# 6502_Debugger_2020-04-26_19-41-09.net
KiCad netlist of a schematic drawn in EasyEDA
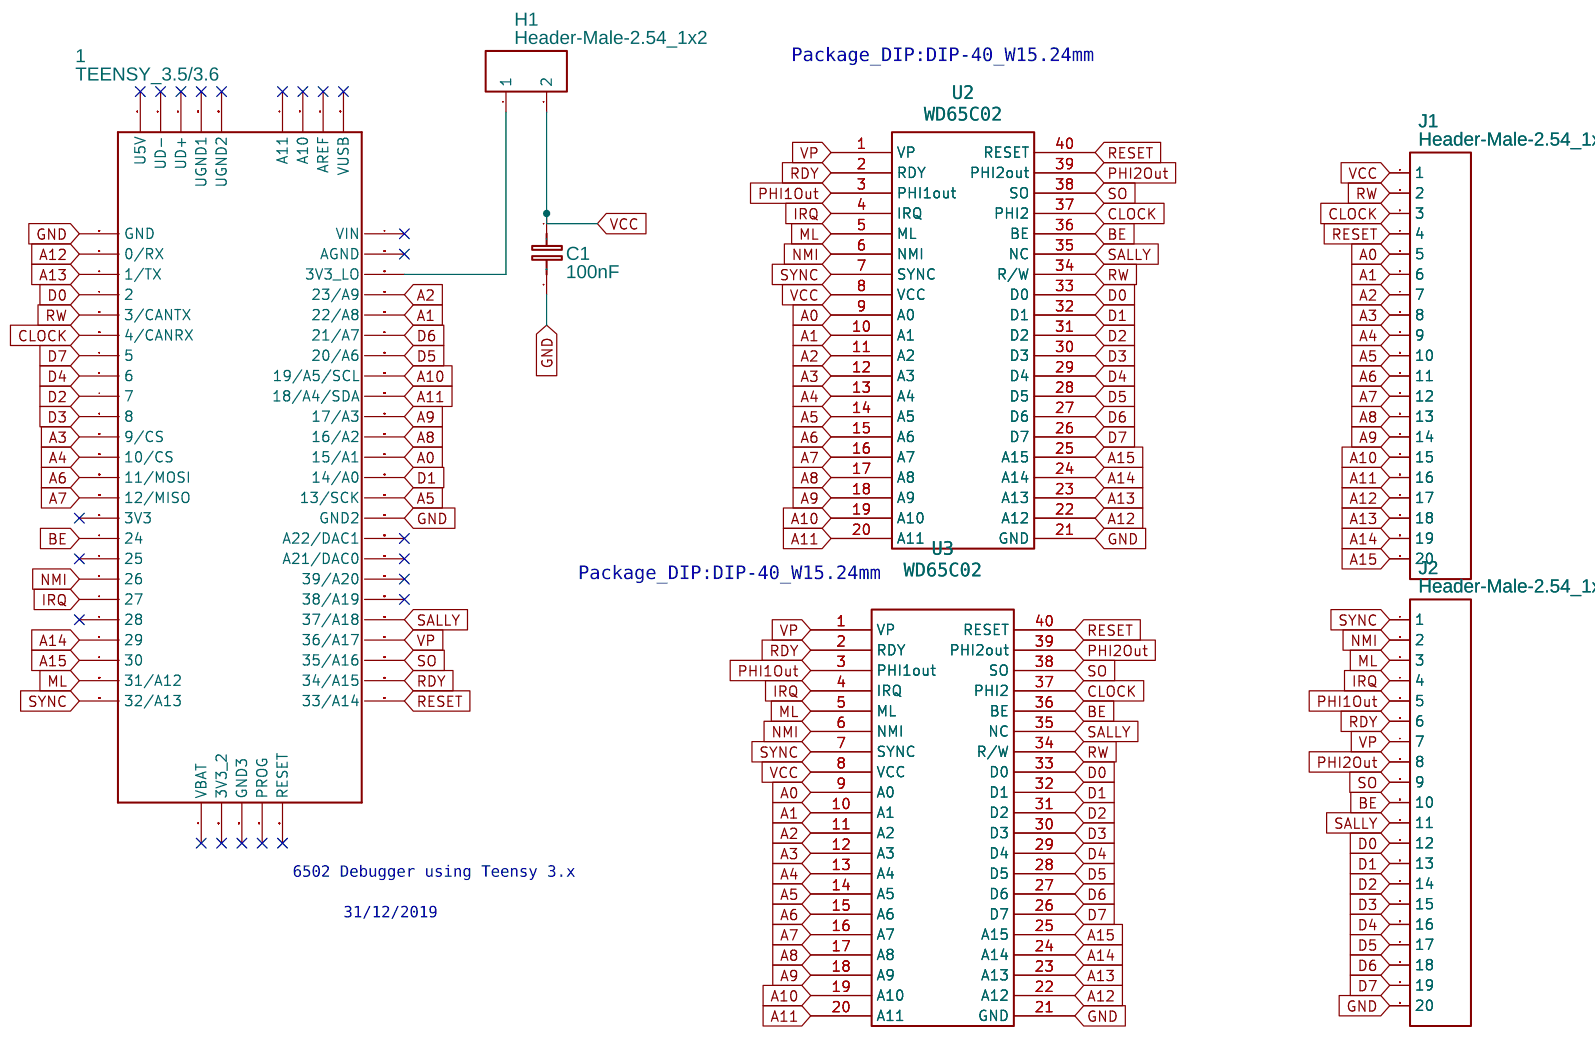
[diagram p0: schematic sheet]

(export (version "E")
  (design (tool "Eeschema 10.0.6"))
  (components
    (comp (ref "1") (value "TEENSY_3.5/3.6") (libsource (lib "") (part "TEENSY_3.5/3.6")))
    (comp (ref "C1") (value "100nF") (libsource (lib "") (part "Cap_RAD-0.1_EU")))
    (comp (ref "H1")
      (value "Header-Male-2.54_1x2")
      (fields (field (name "BOM_Manufacturer Part") "826629-2") (field (name "BOM_Supplier Part") "C86471"))
      (libsource (lib "") (part "Header-Male-2.54_1x2"))
    )
    (comp (ref "J1")
      (value "Header-Male-2.54_1x20")
      (fields
        (field (name "BOM_Manufacturer Part") "2.54mm 1*20PHeader")
        (field (name "BOM_Supplier Part") "C50981")
      )
      (libsource (lib "") (part "Header-Male-2.54_1x20"))
    )
    (comp (ref "J2")
      (value "Header-Male-2.54_1x20")
      (fields
        (field (name "BOM_Manufacturer Part") "2.54mm 1*20PHeader")
        (field (name "BOM_Supplier Part") "C50981")
      )
      (libsource (lib "") (part "Header-Male-2.54_1x20"))
    )
    (comp (ref "U2") (value "WD65C02") (libsource (lib "") (part "Unknown_560_230")))
    (comp (ref "U3") (value "WD65C02") (libsource (lib "") (part "Unknown_550_465")))
  )
  (nets
    (net (code "1") (name "A0") (class "Default")
      (node (ref "1") (pin "15/A1") (pinfunction "15/A1_15/A1") (pintype "bidirectional"))
      (node (ref "J1") (pin "5") (pinfunction "5_5") (pintype "input"))
      (node (ref "U2") (pin "9") (pinfunction "A0_9") (pintype "output"))
      (node (ref "U3") (pin "9") (pinfunction "A0_9") (pintype "output"))
    )
    (net (code "2") (name "A1") (class "Default")
      (node (ref "1") (pin "22/A8") (pinfunction "22/A8_22/A8") (pintype "bidirectional"))
      (node (ref "J1") (pin "6") (pinfunction "6_6") (pintype "input"))
      (node (ref "U2") (pin "10") (pinfunction "A1_10") (pintype "output"))
      (node (ref "U3") (pin "10") (pinfunction "A1_10") (pintype "output"))
    )
    (net (code "3") (name "A2") (class "Default")
      (node (ref "1") (pin "23/A9") (pinfunction "23/A9_23/A9") (pintype "bidirectional"))
      (node (ref "J1") (pin "7") (pinfunction "7_7") (pintype "input"))
      (node (ref "U2") (pin "11") (pinfunction "A2_11") (pintype "output"))
      (node (ref "U3") (pin "11") (pinfunction "A2_11") (pintype "output"))
    )
    (net (code "4") (name "A3") (class "Default")
      (node (ref "1") (pin "9/CS") (pinfunction "9/CS_9/CS") (pintype "bidirectional"))
      (node (ref "J1") (pin "8") (pinfunction "8_8") (pintype "input"))
      (node (ref "U2") (pin "12") (pinfunction "A3_12") (pintype "output"))
      (node (ref "U3") (pin "12") (pinfunction "A3_12") (pintype "output"))
    )
    (net (code "5") (name "A4") (class "Default")
      (node (ref "1") (pin "10/CS") (pinfunction "10/CS_10/CS") (pintype "bidirectional"))
      (node (ref "J1") (pin "9") (pinfunction "9_9") (pintype "input"))
      (node (ref "U2") (pin "13") (pinfunction "A4_13") (pintype "output"))
      (node (ref "U3") (pin "13") (pinfunction "A4_13") (pintype "output"))
    )
    (net (code "6") (name "A5") (class "Default")
      (node (ref "1") (pin "13/SCK") (pinfunction "13/SCK_13/SCK") (pintype "bidirectional"))
      (node (ref "J1") (pin "10") (pinfunction "10_10") (pintype "input"))
      (node (ref "U2") (pin "14") (pinfunction "A5_14") (pintype "output"))
      (node (ref "U3") (pin "14") (pinfunction "A5_14") (pintype "output"))
    )
    (net (code "7") (name "A6") (class "Default")
      (node (ref "1") (pin "11/MOSI") (pinfunction "11/MOSI_11/MOSI") (pintype "bidirectional"))
      (node (ref "J1") (pin "11") (pinfunction "11_11") (pintype "input"))
      (node (ref "U2") (pin "15") (pinfunction "A6_15") (pintype "output"))
      (node (ref "U3") (pin "15") (pinfunction "A6_15") (pintype "output"))
    )
    (net (code "8") (name "A7") (class "Default")
      (node (ref "1") (pin "12/MISO") (pinfunction "12/MISO_12/MISO") (pintype "bidirectional"))
      (node (ref "J1") (pin "12") (pinfunction "12_12") (pintype "input"))
      (node (ref "U2") (pin "16") (pinfunction "A7_16") (pintype "output"))
      (node (ref "U3") (pin "16") (pinfunction "A7_16") (pintype "output"))
    )
    (net (code "9") (name "A8") (class "Default")
      (node (ref "1") (pin "16/A2") (pinfunction "16/A2_16/A2") (pintype "bidirectional"))
      (node (ref "J1") (pin "13") (pinfunction "13_13") (pintype "input"))
      (node (ref "U2") (pin "17") (pinfunction "A8_17") (pintype "output"))
      (node (ref "U3") (pin "17") (pinfunction "A8_17") (pintype "output"))
    )
    (net (code "10") (name "A9") (class "Default")
      (node (ref "1") (pin "17/A3") (pinfunction "17/A3_17/A3") (pintype "bidirectional"))
      (node (ref "J1") (pin "14") (pinfunction "14_14") (pintype "input"))
      (node (ref "U2") (pin "18") (pinfunction "A9_18") (pintype "output"))
      (node (ref "U3") (pin "18") (pinfunction "A9_18") (pintype "output"))
    )
    (net (code "11") (name "A10") (class "Default")
      (node (ref "1") (pin "19/A5/SCL") (pinfunction "19/A5/SCL_19/A5/SCL") (pintype "bidirectional"))
      (node (ref "J1") (pin "15") (pinfunction "15_15") (pintype "input"))
      (node (ref "U2") (pin "19") (pinfunction "A10_19") (pintype "output"))
      (node (ref "U3") (pin "19") (pinfunction "A10_19") (pintype "output"))
    )
    (net (code "12") (name "A11") (class "Default")
      (node (ref "1") (pin "18/A4/SDA") (pinfunction "18/A4/SDA_18/A4/SDA") (pintype "bidirectional"))
      (node (ref "J1") (pin "16") (pinfunction "16_16") (pintype "input"))
      (node (ref "U2") (pin "20") (pinfunction "A11_20") (pintype "output"))
      (node (ref "U3") (pin "20") (pinfunction "A11_20") (pintype "output"))
    )
    (net (code "13") (name "A12") (class "Default")
      (node (ref "1") (pin "0/RX") (pinfunction "0/RX_0/RX") (pintype "bidirectional"))
      (node (ref "J1") (pin "17") (pinfunction "17_17") (pintype "input"))
      (node (ref "U2") (pin "22") (pinfunction "A12_22") (pintype "output"))
      (node (ref "U3") (pin "22") (pinfunction "A12_22") (pintype "output"))
    )
    (net (code "14") (name "A13") (class "Default")
      (node (ref "1") (pin "1/TX") (pinfunction "1/TX_1/TX") (pintype "bidirectional"))
      (node (ref "J1") (pin "18") (pinfunction "18_18") (pintype "input"))
      (node (ref "U2") (pin "23") (pinfunction "A13_23") (pintype "output"))
      (node (ref "U3") (pin "23") (pinfunction "A13_23") (pintype "output"))
    )
    (net (code "15") (name "A14") (class "Default")
      (node (ref "1") (pin "29") (pinfunction "29_29") (pintype "bidirectional"))
      (node (ref "J1") (pin "19") (pinfunction "19_19") (pintype "input"))
      (node (ref "U2") (pin "24") (pinfunction "A14_24") (pintype "output"))
      (node (ref "U3") (pin "24") (pinfunction "A14_24") (pintype "output"))
    )
    (net (code "16") (name "A15") (class "Default")
      (node (ref "1") (pin "30") (pinfunction "30_30") (pintype "bidirectional"))
      (node (ref "J1") (pin "20") (pinfunction "20_20") (pintype "input"))
      (node (ref "U2") (pin "25") (pinfunction "A15_25") (pintype "output"))
      (node (ref "U3") (pin "25") (pinfunction "A15_25") (pintype "output"))
    )
    (net (code "17") (name "BE") (class "Default")
      (node (ref "1") (pin "24") (pinfunction "24_24") (pintype "bidirectional"))
      (node (ref "J2") (pin "10") (pinfunction "10_10") (pintype "input"))
      (node (ref "U2") (pin "36") (pinfunction "BE_36") (pintype "input"))
      (node (ref "U3") (pin "36") (pinfunction "BE_36") (pintype "input"))
    )
    (net (code "18") (name "CLOCK") (class "Default")
      (node (ref "1") (pin "4/CANRX") (pinfunction "4/CANRX_4/CANRX") (pintype "bidirectional"))
      (node (ref "J1") (pin "3") (pinfunction "3_3") (pintype "input"))
      (node (ref "U2") (pin "37") (pinfunction "PHI2_37") (pintype "input"))
      (node (ref "U3") (pin "37") (pinfunction "PHI2_37") (pintype "input"))
    )
    (net (code "19") (name "D0") (class "Default")
      (node (ref "1") (pin "2") (pinfunction "2_2") (pintype "bidirectional"))
      (node (ref "J2") (pin "12") (pinfunction "12_12") (pintype "input"))
      (node (ref "U2") (pin "33") (pinfunction "D0_33") (pintype "bidirectional"))
      (node (ref "U3") (pin "33") (pinfunction "D0_33") (pintype "bidirectional"))
    )
    (net (code "20") (name "D1") (class "Default")
      (node (ref "1") (pin "14/A0") (pinfunction "14/A0_14/A0") (pintype "bidirectional"))
      (node (ref "J2") (pin "13") (pinfunction "13_13") (pintype "input"))
      (node (ref "U2") (pin "32") (pinfunction "D1_32") (pintype "bidirectional"))
      (node (ref "U3") (pin "32") (pinfunction "D1_32") (pintype "bidirectional"))
    )
    (net (code "21") (name "D2") (class "Default")
      (node (ref "1") (pin "7") (pinfunction "7_7") (pintype "bidirectional"))
      (node (ref "J2") (pin "14") (pinfunction "14_14") (pintype "input"))
      (node (ref "U2") (pin "31") (pinfunction "D2_31") (pintype "bidirectional"))
      (node (ref "U3") (pin "31") (pinfunction "D2_31") (pintype "bidirectional"))
    )
    (net (code "22") (name "D3") (class "Default")
      (node (ref "1") (pin "8") (pinfunction "8_8") (pintype "bidirectional"))
      (node (ref "J2") (pin "15") (pinfunction "15_15") (pintype "input"))
      (node (ref "U2") (pin "30") (pinfunction "D3_30") (pintype "bidirectional"))
      (node (ref "U3") (pin "30") (pinfunction "D3_30") (pintype "bidirectional"))
    )
    (net (code "23") (name "D4") (class "Default")
      (node (ref "1") (pin "6") (pinfunction "6_6") (pintype "bidirectional"))
      (node (ref "J2") (pin "16") (pinfunction "16_16") (pintype "input"))
      (node (ref "U2") (pin "29") (pinfunction "D4_29") (pintype "bidirectional"))
      (node (ref "U3") (pin "29") (pinfunction "D4_29") (pintype "bidirectional"))
    )
    (net (code "24") (name "D5") (class "Default")
      (node (ref "1") (pin "20/A6") (pinfunction "20/A6_20/A6") (pintype "bidirectional"))
      (node (ref "J2") (pin "17") (pinfunction "17_17") (pintype "input"))
      (node (ref "U2") (pin "28") (pinfunction "D5_28") (pintype "bidirectional"))
      (node (ref "U3") (pin "28") (pinfunction "D5_28") (pintype "bidirectional"))
    )
    (net (code "25") (name "D6") (class "Default")
      (node (ref "1") (pin "21/A7") (pinfunction "21/A7_21/A7") (pintype "bidirectional"))
      (node (ref "J2") (pin "18") (pinfunction "18_18") (pintype "input"))
      (node (ref "U2") (pin "27") (pinfunction "D6_27") (pintype "bidirectional"))
      (node (ref "U3") (pin "27") (pinfunction "D6_27") (pintype "bidirectional"))
    )
    (net (code "26") (name "D7") (class "Default")
      (node (ref "1") (pin "5") (pinfunction "5_5") (pintype "bidirectional"))
      (node (ref "J2") (pin "19") (pinfunction "19_19") (pintype "input"))
      (node (ref "U2") (pin "26") (pinfunction "D7_26") (pintype "bidirectional"))
      (node (ref "U3") (pin "26") (pinfunction "D7_26") (pintype "bidirectional"))
    )
    (net (code "27") (name "GND") (class "Default")
      (node (ref "1") (pin "GND") (pinfunction "GND_GND") (pintype "bidirectional"))
      (node (ref "1") (pin "GND2") (pinfunction "GND2_GND2") (pintype "bidirectional"))
      (node (ref "C1") (pin "2") (pinfunction "2_2") (pintype "unspecified"))
      (node (ref "J2") (pin "20") (pinfunction "20_20") (pintype "input"))
      (node (ref "U2") (pin "21") (pinfunction "GND_21") (pintype "bidirectional"))
      (node (ref "U3") (pin "21") (pinfunction "GND_21") (pintype "bidirectional"))
    )
    (net (code "28") (name "IRQ") (class "Default")
      (node (ref "1") (pin "27") (pinfunction "27_27") (pintype "bidirectional"))
      (node (ref "J2") (pin "4") (pinfunction "4_4") (pintype "input"))
      (node (ref "U2") (pin "4") (pinfunction "IRQ_4") (pintype "input"))
      (node (ref "U3") (pin "4") (pinfunction "IRQ_4") (pintype "input"))
    )
    (net (code "29") (name "ML") (class "Default")
      (node (ref "1") (pin "31/A12") (pinfunction "31/A12_31/A12") (pintype "bidirectional"))
      (node (ref "J2") (pin "3") (pinfunction "3_3") (pintype "input"))
      (node (ref "U2") (pin "5") (pinfunction "ML_5") (pintype "output"))
      (node (ref "U3") (pin "5") (pinfunction "ML_5") (pintype "output"))
    )
    (net (code "30") (name "NMI") (class "Default")
      (node (ref "1") (pin "26") (pinfunction "26_26") (pintype "bidirectional"))
      (node (ref "J2") (pin "2") (pinfunction "2_2") (pintype "input"))
      (node (ref "U2") (pin "6") (pinfunction "NMI_6") (pintype "input"))
      (node (ref "U3") (pin "6") (pinfunction "NMI_6") (pintype "input"))
    )
    (net (code "31") (name "Net-(1-Pad3V3_LO)") (class "Default")
      (node (ref "1") (pin "3V3_LO") (pinfunction "3V3_LO_3V3_LO") (pintype "bidirectional"))
      (node (ref "H1") (pin "1") (pinfunction "1_1") (pintype "unspecified"))
    )
    (net (code "32") (name "PHI1Out") (class "Default")
      (node (ref "J2") (pin "5") (pinfunction "5_5") (pintype "input"))
      (node (ref "U2") (pin "3") (pinfunction "PHI1out_3") (pintype "output"))
      (node (ref "U3") (pin "3") (pinfunction "PHI1out_3") (pintype "output"))
    )
    (net (code "33") (name "PHI2Out") (class "Default")
      (node (ref "J2") (pin "8") (pinfunction "8_8") (pintype "input"))
      (node (ref "U2") (pin "39") (pinfunction "PHI2out_39") (pintype "output"))
      (node (ref "U3") (pin "39") (pinfunction "PHI2out_39") (pintype "output"))
    )
    (net (code "34") (name "RDY") (class "Default")
      (node (ref "1") (pin "34/A15") (pinfunction "34/A15_34/A15") (pintype "bidirectional"))
      (node (ref "J2") (pin "6") (pinfunction "6_6") (pintype "input"))
      (node (ref "U2") (pin "2") (pinfunction "RDY_2") (pintype "bidirectional"))
      (node (ref "U3") (pin "2") (pinfunction "RDY_2") (pintype "bidirectional"))
    )
    (net (code "35") (name "RESET") (class "Default")
      (node (ref "1") (pin "33/A14") (pinfunction "33/A14_33/A14") (pintype "bidirectional"))
      (node (ref "J1") (pin "4") (pinfunction "4_4") (pintype "input"))
      (node (ref "U2") (pin "40") (pinfunction "RESET_40") (pintype "input"))
      (node (ref "U3") (pin "40") (pinfunction "RESET_40") (pintype "input"))
    )
    (net (code "36") (name "RW") (class "Default")
      (node (ref "1") (pin "3/CANTX") (pinfunction "3/CANTX_3/CANTX") (pintype "bidirectional"))
      (node (ref "J1") (pin "2") (pinfunction "2_2") (pintype "input"))
      (node (ref "U2") (pin "34") (pinfunction "R/W_34") (pintype "output"))
      (node (ref "U3") (pin "34") (pinfunction "R/W_34") (pintype "output"))
    )
    (net (code "37") (name "SALLY") (class "Default")
      (node (ref "1") (pin "37/A18") (pinfunction "37/A18_37/A18") (pintype "bidirectional"))
      (node (ref "J2") (pin "11") (pinfunction "11_11") (pintype "input"))
      (node (ref "U2") (pin "35") (pinfunction "NC_35") (pintype "bidirectional"))
      (node (ref "U3") (pin "35") (pinfunction "NC_35") (pintype "bidirectional"))
    )
    (net (code "38") (name "SO") (class "Default")
      (node (ref "1") (pin "35/A16") (pinfunction "35/A16_35/A16") (pintype "bidirectional"))
      (node (ref "J2") (pin "9") (pinfunction "9_9") (pintype "input"))
      (node (ref "U2") (pin "38") (pinfunction "SO_38") (pintype "output"))
      (node (ref "U3") (pin "38") (pinfunction "SO_38") (pintype "output"))
    )
    (net (code "39") (name "SYNC") (class "Default")
      (node (ref "1") (pin "32/A13") (pinfunction "32/A13_32/A13") (pintype "bidirectional"))
      (node (ref "J2") (pin "1") (pinfunction "1_1") (pintype "input"))
      (node (ref "U2") (pin "7") (pinfunction "SYNC_7") (pintype "output"))
      (node (ref "U3") (pin "7") (pinfunction "SYNC_7") (pintype "output"))
    )
    (net (code "40") (name "VCC") (class "Default")
      (node (ref "C1") (pin "1") (pinfunction "1_1") (pintype "unspecified"))
      (node (ref "H1") (pin "2") (pinfunction "2_2") (pintype "unspecified"))
      (node (ref "J1") (pin "1") (pinfunction "1_1") (pintype "input"))
      (node (ref "U2") (pin "8") (pinfunction "VCC_8") (pintype "bidirectional"))
      (node (ref "U3") (pin "8") (pinfunction "VCC_8") (pintype "bidirectional"))
    )
    (net (code "41") (name "VP") (class "Default")
      (node (ref "1") (pin "36/A17") (pinfunction "36/A17_36/A17") (pintype "bidirectional"))
      (node (ref "J2") (pin "7") (pinfunction "7_7") (pintype "input"))
      (node (ref "U2") (pin "1") (pinfunction "VP_1") (pintype "output"))
      (node (ref "U3") (pin "1") (pinfunction "VP_1") (pintype "output"))
    )
    (net (code "42") (name "unconnected-(1-A21{slash}DAC0-Pad21{slash}DAC0)") (class "Default")
      (node (ref "1") (pin "21/DAC0") (pinfunction "A21/DAC0_21/DAC0") (pintype "bidirectional+no_connect"))
    )
    (net (code "43") (name "unconnected-(1-Pad3V3)") (class "Default")
      (node (ref "1") (pin "3V3") (pinfunction "3V3_3V3") (pintype "bidirectional+no_connect"))
    )
    (net (code "44") (name "unconnected-(1-Pad3V3_2)") (class "Default")
      (node (ref "1") (pin "3V3_2") (pinfunction "3V3_2_3V3_2") (pintype "bidirectional+no_connect"))
    )
    (net (code "45") (name "unconnected-(1-Pad25)") (class "Default")
      (node (ref "1") (pin "25") (pinfunction "25_25") (pintype "bidirectional+no_connect"))
    )
    (net (code "46") (name "unconnected-(1-Pad28)") (class "Default")
      (node (ref "1") (pin "28") (pinfunction "28_28") (pintype "bidirectional+no_connect"))
    )
    (net (code "47") (name "unconnected-(1-Pad38{slash}A19)") (class "Default")
      (node (ref "1") (pin "38/A19") (pinfunction "38/A19_38/A19") (pintype "bidirectional+no_connect"))
    )
    (net (code "48") (name "unconnected-(1-Pad39{slash}A20)") (class "Default")
      (node (ref "1") (pin "39/A20") (pinfunction "39/A20_39/A20") (pintype "bidirectional+no_connect"))
    )
    (net (code "49") (name "unconnected-(1-PadA10)") (class "Default")
      (node (ref "1") (pin "A10") (pinfunction "A10_A10") (pintype "bidirectional+no_connect"))
    )
    (net (code "50") (name "unconnected-(1-PadA11)") (class "Default")
      (node (ref "1") (pin "A11") (pinfunction "A11_A11") (pintype "bidirectional+no_connect"))
    )
    (net (code "51") (name "unconnected-(1-PadA22{slash}DAC1)") (class "Default")
      (node (ref "1") (pin "A22/DAC1") (pinfunction "A22/DAC1_A22/DAC1") (pintype "bidirectional+no_connect"))
    )
    (net (code "52") (name "unconnected-(1-PadAGND)") (class "Default")
      (node (ref "1") (pin "AGND") (pinfunction "AGND_AGND") (pintype "bidirectional+no_connect"))
    )
    (net (code "53") (name "unconnected-(1-PadAREF)") (class "Default")
      (node (ref "1") (pin "AREF") (pinfunction "AREF_AREF") (pintype "bidirectional+no_connect"))
    )
    (net (code "54") (name "unconnected-(1-PadGND3)") (class "Default")
      (node (ref "1") (pin "GND3") (pinfunction "GND3_GND3") (pintype "bidirectional+no_connect"))
    )
    (net (code "55") (name "unconnected-(1-PadPROG)") (class "Default")
      (node (ref "1") (pin "PROG") (pinfunction "PROG_PROG") (pintype "bidirectional+no_connect"))
    )
    (net (code "56") (name "unconnected-(1-PadRESET)") (class "Default")
      (node (ref "1") (pin "RESET") (pinfunction "RESET_RESET") (pintype "bidirectional+no_connect"))
    )
    (net (code "57") (name "unconnected-(1-PadU5V)") (class "Default")
      (node (ref "1") (pin "U5V") (pinfunction "U5V_U5V") (pintype "bidirectional+no_connect"))
    )
    (net (code "58") (name "unconnected-(1-PadUD+)") (class "Default")
      (node (ref "1") (pin "UD+") (pinfunction "UD+_UD+") (pintype "bidirectional+no_connect"))
    )
    (net (code "59") (name "unconnected-(1-PadUD-)") (class "Default")
      (node (ref "1") (pin "UD-") (pinfunction "UD-_UD-") (pintype "bidirectional+no_connect"))
    )
    (net (code "60") (name "unconnected-(1-PadUGND1)") (class "Default")
      (node (ref "1") (pin "UGND1") (pinfunction "UGND1_UGND1") (pintype "bidirectional+no_connect"))
    )
    (net (code "61") (name "unconnected-(1-PadUGND2)") (class "Default")
      (node (ref "1") (pin "UGND2") (pinfunction "UGND2_UGND2") (pintype "bidirectional+no_connect"))
    )
    (net (code "62") (name "unconnected-(1-PadVBAT)") (class "Default")
      (node (ref "1") (pin "VBAT") (pinfunction "VBAT_VBAT") (pintype "bidirectional+no_connect"))
    )
    (net (code "63") (name "unconnected-(1-PadVIN)") (class "Default")
      (node (ref "1") (pin "VIN") (pinfunction "VIN_VIN") (pintype "bidirectional+no_connect"))
    )
    (net (code "64") (name "unconnected-(1-PadVUSB)") (class "Default")
      (node (ref "1") (pin "VUSB") (pinfunction "VUSB_VUSB") (pintype "bidirectional+no_connect"))
    )
  )
)
